# rev.net
KiCad netlist of a schematic drawn in Altium Designer
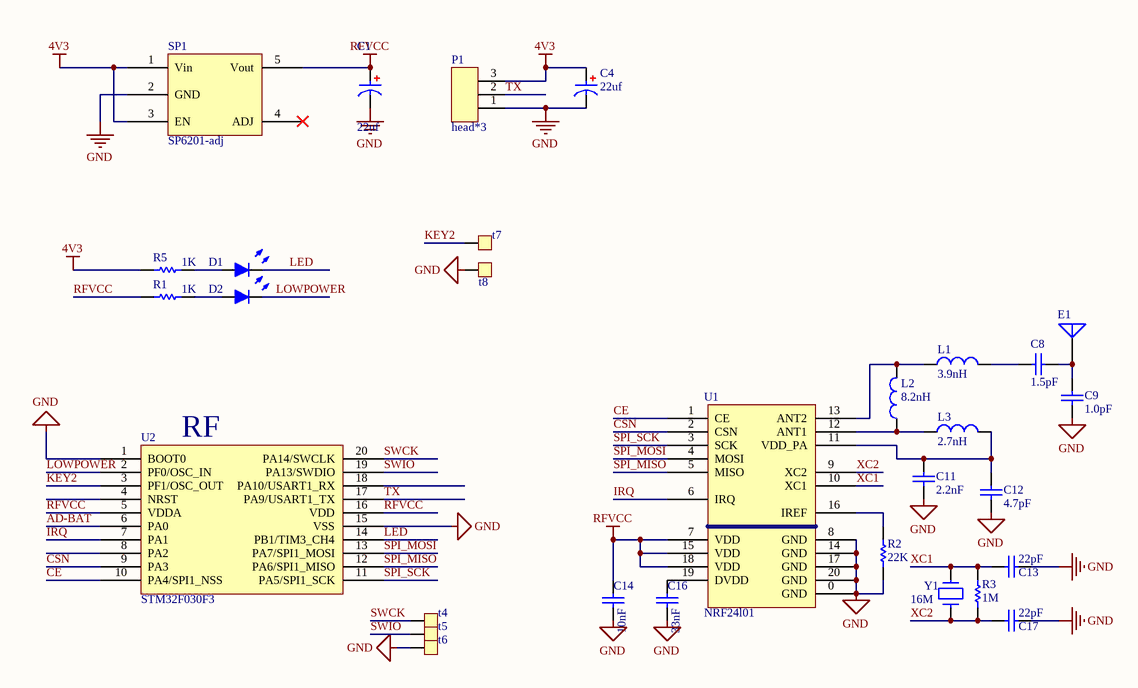
[diagram p0: rev.SchDoc]

(export (version "E")
  (design (tool "Eeschema 10.0.6"))
  (components
    (comp (ref "C1")
      (value "22uf")
      (footprint "0603R")
      (fields (field (name "ALTIUM_UNNAMED_1") "22uf"))
      (libsource (lib "OKmeSchLibrary") (part "C100uF"))
    )
    (comp (ref "C4")
      (value "22uf")
      (footprint "0603R")
      (fields (field (name "ALTIUM_UNNAMED_1") "22uf"))
      (libsource (lib "OKmeSchLibrary") (part "C100uF"))
    )
    (comp (ref "C8")
      (value "1.5pF")
      (footprint "0402")
      (fields (field (name "ALTIUM_UNNAMED_1") "1.5pF"))
      (libsource (lib "OKmeSchLibrary") (part "C0.1uF"))
    )
    (comp (ref "C9")
      (value "1.0pF")
      (footprint "0402")
      (fields (field (name "ALTIUM_UNNAMED_1") "1.0pF"))
      (libsource (lib "OKmeSchLibrary") (part "C0.1uF"))
    )
    (comp (ref "C11")
      (value "2.2nF")
      (footprint "0402")
      (fields (field (name "ALTIUM_UNNAMED_1") "2.2nF"))
      (libsource (lib "OKmeSchLibrary") (part "C0.1uF"))
    )
    (comp (ref "C12")
      (value "4.7pF")
      (footprint "0402")
      (fields (field (name "ALTIUM_UNNAMED_1") "4.7pF"))
      (libsource (lib "OKmeSchLibrary") (part "C0.1uF"))
    )
    (comp (ref "C13")
      (value "22pF")
      (footprint "0402")
      (fields (field (name "ALTIUM_UNNAMED_1") "22pF"))
      (libsource (lib "OKmeSchLibrary") (part "C0.1uF"))
    )
    (comp (ref "C14")
      (value "10nF")
      (footprint "0402")
      (fields (field (name "ALTIUM_UNNAMED_1") "10nF"))
      (libsource (lib "OKmeSchLibrary") (part "C0.1uF"))
    )
    (comp (ref "C16")
      (value "33nF")
      (footprint "0402")
      (fields (field (name "ALTIUM_UNNAMED_1") "33nF"))
      (libsource (lib "OKmeSchLibrary") (part "C0.1uF"))
    )
    (comp (ref "C17")
      (value "22pF")
      (footprint "0402")
      (fields (field (name "ALTIUM_UNNAMED_1") "22pF"))
      (libsource (lib "OKmeSchLibrary") (part "C0.1uF"))
    )
    (comp (ref "D1") (value "LED-R") (footprint "LED") (libsource (lib "OKmeSchLibrary") (part "LED")))
    (comp (ref "D2") (value "LED-G") (footprint "LED") (libsource (lib "OKmeSchLibrary") (part "LED")))
    (comp (ref "E1")
      (value "Antenna")
      (footprint "ANT6520")
      (description "Generic Antenna")
      (fields (field (name "PUBLISHER") "Altium Limited"))
      (libsource (lib "Miscellaneous Devices") (part "Antenna"))
    )
    (comp (ref "L1")
      (value "3.9nH")
      (footprint "0402")
      (fields (field (name "ALTIUM_UNNAMED_1") "3.9nH"))
      (libsource (lib "") (part "Inductor-100uH_1"))
    )
    (comp (ref "L2")
      (value "8.2nH")
      (footprint "0402")
      (fields (field (name "ALTIUM_UNNAMED_1") "8.2nH"))
      (libsource (lib "") (part "Inductor-100uH_1"))
    )
    (comp (ref "L3")
      (value "2.7nH")
      (footprint "0402")
      (fields (field (name "ALTIUM_UNNAMED_1") "2.7nH"))
      (libsource (lib "OKmeSchLibrary") (part "Inductor-100uH"))
    )
    (comp (ref "P1")
      (value "head*3")
      (footprint "head*3 - duplicate")
      (libsource (lib "OKmeSchLibrary") (part "head*3"))
    )
    (comp (ref "R1")
      (value "R1K")
      (footprint "0402")
      (fields (field (name "ALTIUM_UNNAMED_1") "1K"))
      (libsource (lib "OKmeSchLibrary") (part "R1K"))
    )
    (comp (ref "R2")
      (value "22K")
      (footprint "0402")
      (fields (field (name "ALTIUM_UNNAMED_1") "22K"))
      (libsource (lib "OKmeSchLibrary") (part "R10K"))
    )
    (comp (ref "R3")
      (value "R1M")
      (footprint "0402")
      (fields (field (name "ALTIUM_UNNAMED_1") "1M"))
      (libsource (lib "OKmeSchLibrary") (part "R10K"))
    )
    (comp (ref "R5")
      (value "R1K")
      (footprint "0402")
      (fields (field (name "ALTIUM_UNNAMED_1") "1K"))
      (libsource (lib "OKmeSchLibrary") (part "R1K"))
    )
    (comp (ref "SP1")
      (value "SP6201-adj")
      (footprint "SOT23-5")
      (libsource (lib "OKmeSchLibrary") (part "SP6201"))
    )
    (comp (ref "t4") (value "TP") (footprint "TESTPOINT") (libsource (lib "OKmeSchLibrary") (part "TP")))
    (comp (ref "t5") (value "TP") (footprint "TESTPOINT") (libsource (lib "OKmeSchLibrary") (part "TP")))
    (comp (ref "t6") (value "TP") (footprint "TESTPOINT") (libsource (lib "OKmeSchLibrary") (part "TP")))
    (comp (ref "t7") (value "TP") (footprint "TESTPOINT") (libsource (lib "OKmeSchLibrary") (part "TP")))
    (comp (ref "t8") (value "TP") (footprint "TESTPOINT") (libsource (lib "OKmeSchLibrary") (part "TP")))
    (comp (ref "U1")
      (value "NRF24l01")
      (footprint "QFN20-4X4")
      (libsource (lib "OKmeSchLibrary") (part "NRF24l01"))
    )
    (comp (ref "U2")
      (value "STM32F030F3")
      (footprint "TSSOP20")
      (libsource (lib "OKmeSchLibrary") (part "STM32F030F4"))
    )
    (comp (ref "Y1")
      (value "16M")
      (footprint "XTAL3225")
      (description "Crystal")
      (libsource (lib "*") (part "CRYSTAL"))
    )
  )
  (nets
    (net (code "1") (name "/AD-BAT") (class "Default")
      (node (ref "U2") (pin "6") (pinfunction "PA0_6") (pintype "passive"))
    )
    (net (code "2") (name "/CE") (class "Default")
      (node (ref "U1") (pin "1") (pinfunction "CE_1") (pintype "passive"))
      (node (ref "U2") (pin "10") (pinfunction "PA4/SPI1_NSS_10") (pintype "passive"))
    )
    (net (code "3") (name "/CSN") (class "Default")
      (node (ref "U1") (pin "2") (pinfunction "CSN_2") (pintype "passive"))
      (node (ref "U2") (pin "9") (pinfunction "PA3_9") (pintype "passive"))
    )
    (net (code "4") (name "/IRQ") (class "Default")
      (node (ref "U1") (pin "6") (pinfunction "IRQ_6") (pintype "passive"))
      (node (ref "U2") (pin "7") (pinfunction "PA1_7") (pintype "passive"))
    )
    (net (code "5") (name "/KEY2") (class "Default")
      (node (ref "U2") (pin "3") (pinfunction "PF1/OSC_OUT_3") (pintype "passive"))
      (node (ref "t7") (pin "1") (pinfunction "R_1") (pintype "passive"))
    )
    (net (code "6") (name "/LED") (class "Default")
      (node (ref "D1") (pin "2") (pinfunction "K_2") (pintype "passive"))
      (node (ref "U2") (pin "14") (pinfunction "PB1/TIM3_CH4_14") (pintype "passive"))
    )
    (net (code "7") (name "/LOWPOWER") (class "Default")
      (node (ref "D2") (pin "2") (pinfunction "K_2") (pintype "passive"))
      (node (ref "U2") (pin "2") (pinfunction "PF0/OSC_IN_2") (pintype "passive"))
    )
    (net (code "8") (name "/SPI_MISO") (class "Default")
      (node (ref "U1") (pin "5") (pinfunction "MISO_5") (pintype "passive"))
      (node (ref "U2") (pin "12") (pinfunction "PA6/SPI1_MISO_12") (pintype "passive"))
    )
    (net (code "9") (name "/SPI_MOSI") (class "Default")
      (node (ref "U1") (pin "4") (pinfunction "MOSI_4") (pintype "passive"))
      (node (ref "U2") (pin "13") (pinfunction "PA7/SPI1_MOSI_13") (pintype "passive"))
    )
    (net (code "10") (name "/SPI_SCK") (class "Default")
      (node (ref "U1") (pin "3") (pinfunction "SCK_3") (pintype "passive"))
      (node (ref "U2") (pin "11") (pinfunction "PA5/SPI1_SCK_11") (pintype "passive"))
    )
    (net (code "11") (name "/SWCK") (class "Default")
      (node (ref "U2") (pin "20") (pinfunction "PA14/SWCLK_20") (pintype "passive"))
      (node (ref "t4") (pin "1") (pinfunction "R_1") (pintype "passive"))
    )
    (net (code "12") (name "/SWIO") (class "Default")
      (node (ref "U2") (pin "19") (pinfunction "PA13/SWDIO_19") (pintype "passive"))
      (node (ref "t5") (pin "1") (pinfunction "R_1") (pintype "passive"))
    )
    (net (code "13") (name "/TX") (class "Default")
      (node (ref "P1") (pin "2") (pinfunction "2_2") (pintype "passive"))
      (node (ref "U2") (pin "17") (pinfunction "PA9/USART1_TX_17") (pintype "passive"))
    )
    (net (code "14") (name "/XC1") (class "Default")
      (node (ref "C13") (pin "2") (pinfunction "2_2") (pintype "passive"))
      (node (ref "R3") (pin "1") (pinfunction "1_1") (pintype "passive"))
      (node (ref "U1") (pin "10") (pinfunction "XC1_10") (pintype "passive"))
      (node (ref "Y1") (pin "3") (pinfunction "3_3") (pintype "passive"))
    )
    (net (code "15") (name "/XC2") (class "Default")
      (node (ref "C17") (pin "2") (pinfunction "2_2") (pintype "passive"))
      (node (ref "R3") (pin "2") (pinfunction "2_2") (pintype "passive"))
      (node (ref "U1") (pin "9") (pinfunction "XC2_9") (pintype "passive"))
      (node (ref "Y1") (pin "1") (pinfunction "1_1") (pintype "passive"))
    )
    (net (code "16") (name "4V3") (class "Default")
      (node (ref "C4") (pin "1") (pinfunction "1_1") (pintype "passive"))
      (node (ref "P1") (pin "3") (pinfunction "3_3") (pintype "passive"))
      (node (ref "R5") (pin "1") (pinfunction "1_1") (pintype "passive"))
      (node (ref "SP1") (pin "1") (pinfunction "Vin_1") (pintype "power_in"))
      (node (ref "SP1") (pin "3") (pinfunction "EN_3") (pintype "passive"))
    )
    (net (code "17") (name "GND") (class "Default")
      (node (ref "C1") (pin "2") (pinfunction "2_2") (pintype "passive"))
      (node (ref "C11") (pin "1") (pinfunction "1_1") (pintype "passive"))
      (node (ref "C12") (pin "1") (pinfunction "1_1") (pintype "passive"))
      (node (ref "C13") (pin "1") (pinfunction "1_1") (pintype "passive"))
      (node (ref "C14") (pin "1") (pinfunction "1_1") (pintype "passive"))
      (node (ref "C16") (pin "1") (pinfunction "1_1") (pintype "passive"))
      (node (ref "C17") (pin "1") (pinfunction "1_1") (pintype "passive"))
      (node (ref "C4") (pin "2") (pinfunction "2_2") (pintype "passive"))
      (node (ref "C9") (pin "1") (pinfunction "1_1") (pintype "passive"))
      (node (ref "P1") (pin "1") (pinfunction "1_1") (pintype "passive"))
      (node (ref "R2") (pin "2") (pinfunction "2_2") (pintype "passive"))
      (node (ref "SP1") (pin "2") (pinfunction "GND_2") (pintype "power_in"))
      (node (ref "U1") (pin "0") (pinfunction "GND_0") (pintype "passive"))
      (node (ref "U1") (pin "14") (pinfunction "GND_14") (pintype "passive"))
      (node (ref "U1") (pin "17") (pinfunction "GND_17") (pintype "passive"))
      (node (ref "U1") (pin "20") (pinfunction "GND_20") (pintype "passive"))
      (node (ref "U1") (pin "8") (pinfunction "GND_8") (pintype "passive"))
      (node (ref "U2") (pin "1") (pinfunction "BOOT0_1") (pintype "passive"))
      (node (ref "U2") (pin "15") (pinfunction "VSS_15") (pintype "passive"))
      (node (ref "t6") (pin "1") (pinfunction "R_1") (pintype "passive"))
      (node (ref "t8") (pin "1") (pinfunction "R_1") (pintype "passive"))
    )
    (net (code "18") (name "Net-(C8-Pad1)") (class "Default")
      (node (ref "C8") (pin "1") (pinfunction "1_1") (pintype "passive"))
      (node (ref "L1") (pin "2") (pinfunction "2_2") (pintype "passive"))
    )
    (net (code "19") (name "Net-(D1-A)") (class "Default")
      (node (ref "D1") (pin "1") (pinfunction "A_1") (pintype "passive"))
      (node (ref "R5") (pin "2") (pinfunction "2_2") (pintype "passive"))
    )
    (net (code "20") (name "Net-(D2-A)") (class "Default")
      (node (ref "D2") (pin "1") (pinfunction "A_1") (pintype "passive"))
      (node (ref "R1") (pin "2") (pinfunction "2_2") (pintype "passive"))
    )
    (net (code "21") (name "Net-(E1-A)") (class "Default")
      (node (ref "C8") (pin "2") (pinfunction "2_2") (pintype "passive"))
      (node (ref "C9") (pin "2") (pinfunction "2_2") (pintype "passive"))
      (node (ref "E1") (pin "1") (pinfunction "A_1") (pintype "passive"))
    )
    (net (code "22") (name "Net-(U1-ANT1)") (class "Default")
      (node (ref "L2") (pin "1") (pinfunction "1_1") (pintype "passive"))
      (node (ref "L3") (pin "2") (pinfunction "2_2") (pintype "passive"))
      (node (ref "U1") (pin "12") (pinfunction "ANT1_12") (pintype "passive"))
    )
    (net (code "23") (name "Net-(U1-ANT2)") (class "Default")
      (node (ref "L1") (pin "1") (pinfunction "1_1") (pintype "passive"))
      (node (ref "L2") (pin "2") (pinfunction "2_2") (pintype "passive"))
      (node (ref "U1") (pin "13") (pinfunction "ANT2_13") (pintype "passive"))
    )
    (net (code "24") (name "Net-(U1-DVDD)") (class "Default")
      (node (ref "C16") (pin "2") (pinfunction "2_2") (pintype "passive"))
      (node (ref "U1") (pin "19") (pinfunction "DVDD_19") (pintype "passive"))
    )
    (net (code "25") (name "Net-(U1-IREF)") (class "Default")
      (node (ref "R2") (pin "1") (pinfunction "1_1") (pintype "passive"))
      (node (ref "U1") (pin "16") (pinfunction "IREF_16") (pintype "passive"))
    )
    (net (code "26") (name "Net-(U1-VDD_PA)") (class "Default")
      (node (ref "C11") (pin "2") (pinfunction "2_2") (pintype "passive"))
      (node (ref "C12") (pin "2") (pinfunction "2_2") (pintype "passive"))
      (node (ref "L3") (pin "1") (pinfunction "1_1") (pintype "passive"))
      (node (ref "U1") (pin "11") (pinfunction "VDD_PA_11") (pintype "passive"))
    )
    (net (code "27") (name "RFVCC") (class "Default")
      (node (ref "C1") (pin "1") (pinfunction "1_1") (pintype "passive"))
      (node (ref "C14") (pin "2") (pinfunction "2_2") (pintype "passive"))
      (node (ref "R1") (pin "1") (pinfunction "1_1") (pintype "passive"))
      (node (ref "SP1") (pin "5") (pinfunction "Vout_5") (pintype "power_in"))
      (node (ref "U1") (pin "15") (pinfunction "VDD_15") (pintype "passive"))
      (node (ref "U1") (pin "18") (pinfunction "VDD_18") (pintype "passive"))
      (node (ref "U1") (pin "7") (pinfunction "VDD_7") (pintype "passive"))
      (node (ref "U2") (pin "16") (pinfunction "VDD_16") (pintype "passive"))
      (node (ref "U2") (pin "5") (pinfunction "VDDA_5") (pintype "passive"))
    )
    (net (code "28") (name "unconnected-(SP1-ADJ-Pad4)") (class "Default")
      (node (ref "SP1") (pin "4") (pinfunction "ADJ_4") (pintype "passive+no_connect"))
    )
    (net (code "29") (name "unconnected-(U2-NRST-Pad4)") (class "Default")
      (node (ref "U2") (pin "4") (pinfunction "NRST_4") (pintype "passive"))
    )
    (net (code "30") (name "unconnected-(U2-PA2-Pad8)") (class "Default")
      (node (ref "U2") (pin "8") (pinfunction "PA2_8") (pintype "passive"))
    )
    (net (code "31") (name "unconnected-(U2-PA10{slash}USART1_RX-Pad18)") (class "Default")
      (node (ref "U2") (pin "18") (pinfunction "PA10/USART1_RX_18") (pintype "passive"))
    )
  )
)
